# usb-led.net
KiCad netlist of a schematic drawn in EAGLE
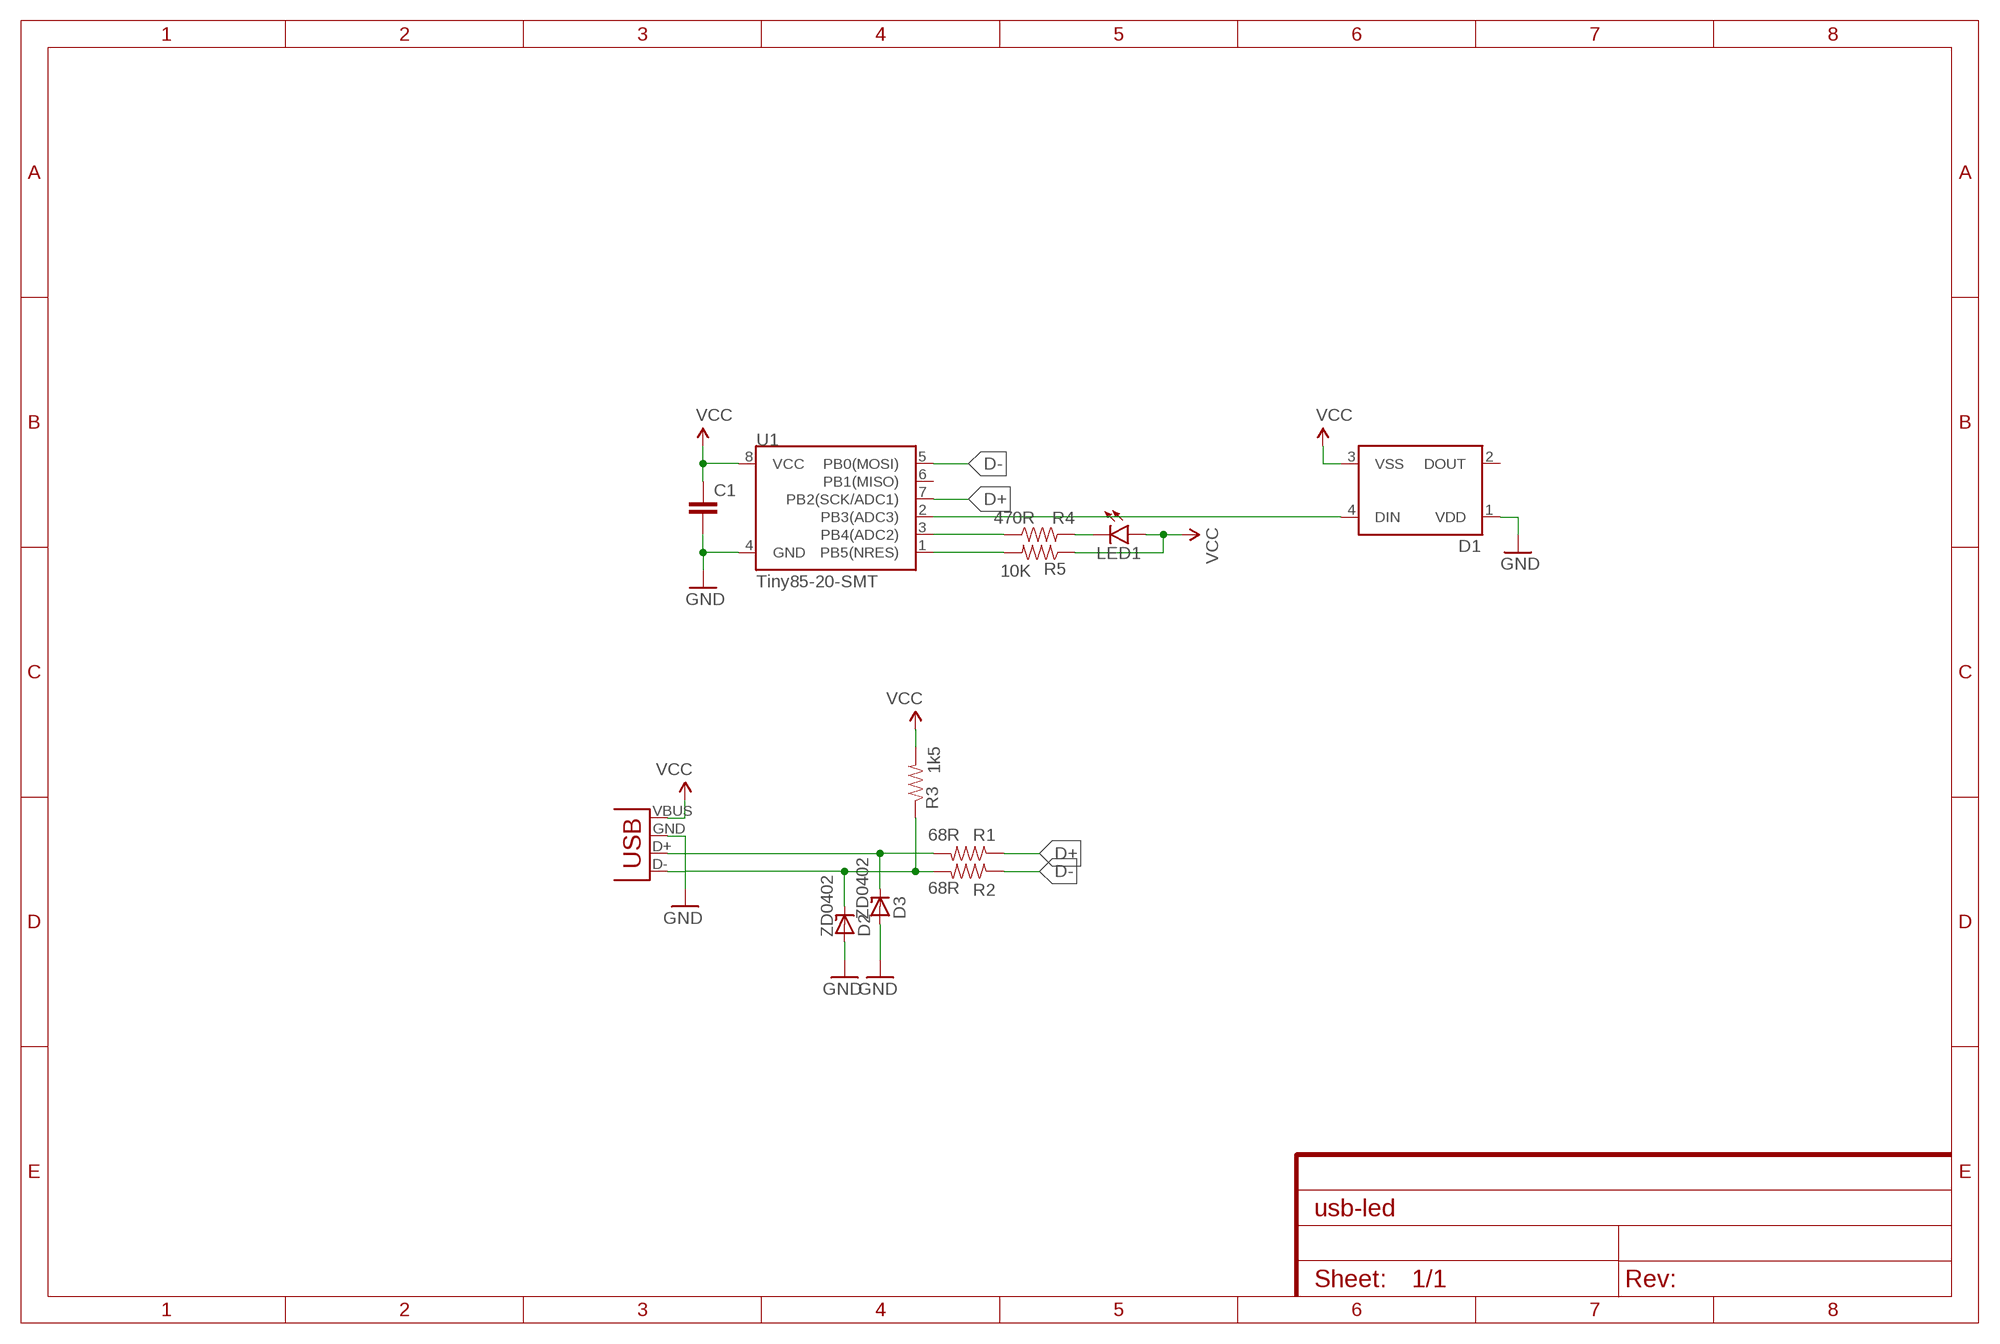
[diagram p0: schematic, sheet 1]

(export (version "E")
  (design (tool "Eeschema 10.0.6"))
  (components
    (comp (ref "C1")
      (value "CAP0805")
      (footprint "eagle-import:0805")
      (libsource (lib "eagle-import") (part "CAP0805"))
    )
    (comp (ref "D1")
      (value "WS2812B")
      (footprint "eagle-import:WS2812B")
      (libsource (lib "eagle-import") (part "WS2812B"))
    )
    (comp (ref "D2")
      (value "ZD0402")
      (footprint "eagle-import:ZD0402")
      (libsource (lib "eagle-import") (part "ZD0402"))
    )
    (comp (ref "D3")
      (value "ZD0402")
      (footprint "eagle-import:ZD0402")
      (libsource (lib "eagle-import") (part "ZD0402"))
    )
    (comp (ref "JP2")
      (value "USB-A-H")
      (footprint "eagle-import:USB-A-H")
      (libsource (lib "eagle-import") (part "USB-A-H"))
    )
    (comp (ref "LED1")
      (value "LED0603")
      (footprint "eagle-import:LED-0603")
      (libsource (lib "eagle-import") (part "LED0603"))
    )
    (comp (ref "R1")
      (value "68R")
      (footprint "eagle-import:0402-RES")
      (libsource (lib "eagle-import") (part "RESISTOR0402-RES"))
    )
    (comp (ref "R2")
      (value "68R")
      (footprint "eagle-import:0402-RES")
      (libsource (lib "eagle-import") (part "RESISTOR0402-RES"))
    )
    (comp (ref "R3")
      (value "1k5")
      (footprint "eagle-import:0402-RES")
      (libsource (lib "eagle-import") (part "RESISTOR0402-RES"))
    )
    (comp (ref "R4")
      (value "470R")
      (footprint "eagle-import:0603-RES")
      (libsource (lib "eagle-import") (part "RESISTOR0603"))
    )
    (comp (ref "R5")
      (value "10K")
      (footprint "eagle-import:0402-RES")
      (libsource (lib "eagle-import") (part "RESISTOR0402-RES"))
    )
    (comp (ref "U1")
      (value "Tiny85-20-SMT")
      (footprint "eagle-import:SO08-EIAJ")
      (libsource (lib "eagle-import") (part "ATTINY45TINY85-20-SMT"))
    )
  )
  (nets
    (net (code "1") (name "/N$2") (class "Default")
      (node (ref "D2") (pin "K") (pinfunction "C_K") (pintype "passive"))
      (node (ref "JP2") (pin "D-") (pinfunction "D+_D-") (pintype "bidirectional"))
      (node (ref "R2") (pin "2") (pinfunction "2_2") (pintype "passive"))
      (node (ref "R3") (pin "1") (pinfunction "1_1") (pintype "passive"))
    )
    (net (code "2") (name "D+") (class "Default")
      (node (ref "R1") (pin "1") (pinfunction "1_1") (pintype "passive"))
      (node (ref "U1") (pin "7") (pinfunction "PB2(SCK/ADC1)_7") (pintype "bidirectional"))
    )
    (net (code "3") (name "D-") (class "Default")
      (node (ref "R2") (pin "1") (pinfunction "1_1") (pintype "passive"))
      (node (ref "U1") (pin "5") (pinfunction "PB0(MOSI)_5") (pintype "bidirectional"))
    )
    (net (code "4") (name "GND") (class "Default")
      (node (ref "C1") (pin "2") (pinfunction "2_2") (pintype "passive"))
      (node (ref "D1") (pin "1") (pinfunction "VDD_1") (pintype "power_in"))
      (node (ref "D2") (pin "A") (pinfunction "A_A") (pintype "passive"))
      (node (ref "D3") (pin "A") (pinfunction "A_A") (pintype "passive"))
      (node (ref "JP2") (pin "GND") (pinfunction "VBUS_GND") (pintype "bidirectional"))
      (node (ref "U1") (pin "4") (pinfunction "GND_4") (pintype "bidirectional"))
    )
    (net (code "5") (name "Net-(D1-DIN)") (class "Default")
      (node (ref "D1") (pin "4") (pinfunction "DIN_4") (pintype "input"))
      (node (ref "U1") (pin "2") (pinfunction "PB3(ADC3)_2") (pintype "bidirectional"))
    )
    (net (code "6") (name "Net-(D3-C)") (class "Default")
      (node (ref "D3") (pin "K") (pinfunction "C_K") (pintype "passive"))
      (node (ref "JP2") (pin "D+") (pinfunction "D-_D+") (pintype "bidirectional"))
      (node (ref "R1") (pin "2") (pinfunction "2_2") (pintype "passive"))
    )
    (net (code "7") (name "Net-(LED1-PadC)") (class "Default")
      (node (ref "LED1") (pin "C") (pinfunction "C_C") (pintype "passive"))
      (node (ref "R4") (pin "2") (pinfunction "2_2") (pintype "passive"))
    )
    (net (code "8") (name "Net-(U1-PB4(ADC2))") (class "Default")
      (node (ref "R4") (pin "1") (pinfunction "1_1") (pintype "passive"))
      (node (ref "U1") (pin "3") (pinfunction "PB4(ADC2)_3") (pintype "bidirectional"))
    )
    (net (code "9") (name "Net-(U1-PB5(NRES))") (class "Default")
      (node (ref "R5") (pin "2") (pinfunction "2_2") (pintype "passive"))
      (node (ref "U1") (pin "1") (pinfunction "PB5(NRES)_1") (pintype "bidirectional"))
    )
    (net (code "10") (name "VCC") (class "Default")
      (node (ref "C1") (pin "1") (pinfunction "1_1") (pintype "passive"))
      (node (ref "D1") (pin "3") (pinfunction "VSS_3") (pintype "power_in"))
      (node (ref "JP2") (pin "VBUS") (pinfunction "GND_VBUS") (pintype "bidirectional"))
      (node (ref "LED1") (pin "A") (pinfunction "A_A") (pintype "passive"))
      (node (ref "R3") (pin "2") (pinfunction "2_2") (pintype "passive"))
      (node (ref "R5") (pin "1") (pinfunction "1_1") (pintype "passive"))
      (node (ref "U1") (pin "8") (pinfunction "VCC_8") (pintype "bidirectional"))
    )
    (net (code "11") (name "unconnected-(D1-DOUT-Pad2)") (class "Default")
      (node (ref "D1") (pin "2") (pinfunction "DOUT_2") (pintype "output"))
    )
    (net (code "12") (name "unconnected-(U1-PB1(MISO)-Pad6)") (class "Default")
      (node (ref "U1") (pin "6") (pinfunction "PB1(MISO)_6") (pintype "bidirectional"))
    )
  )
)
